# DRV8833.net
KiCad netlist of a schematic drawn in Altium Designer
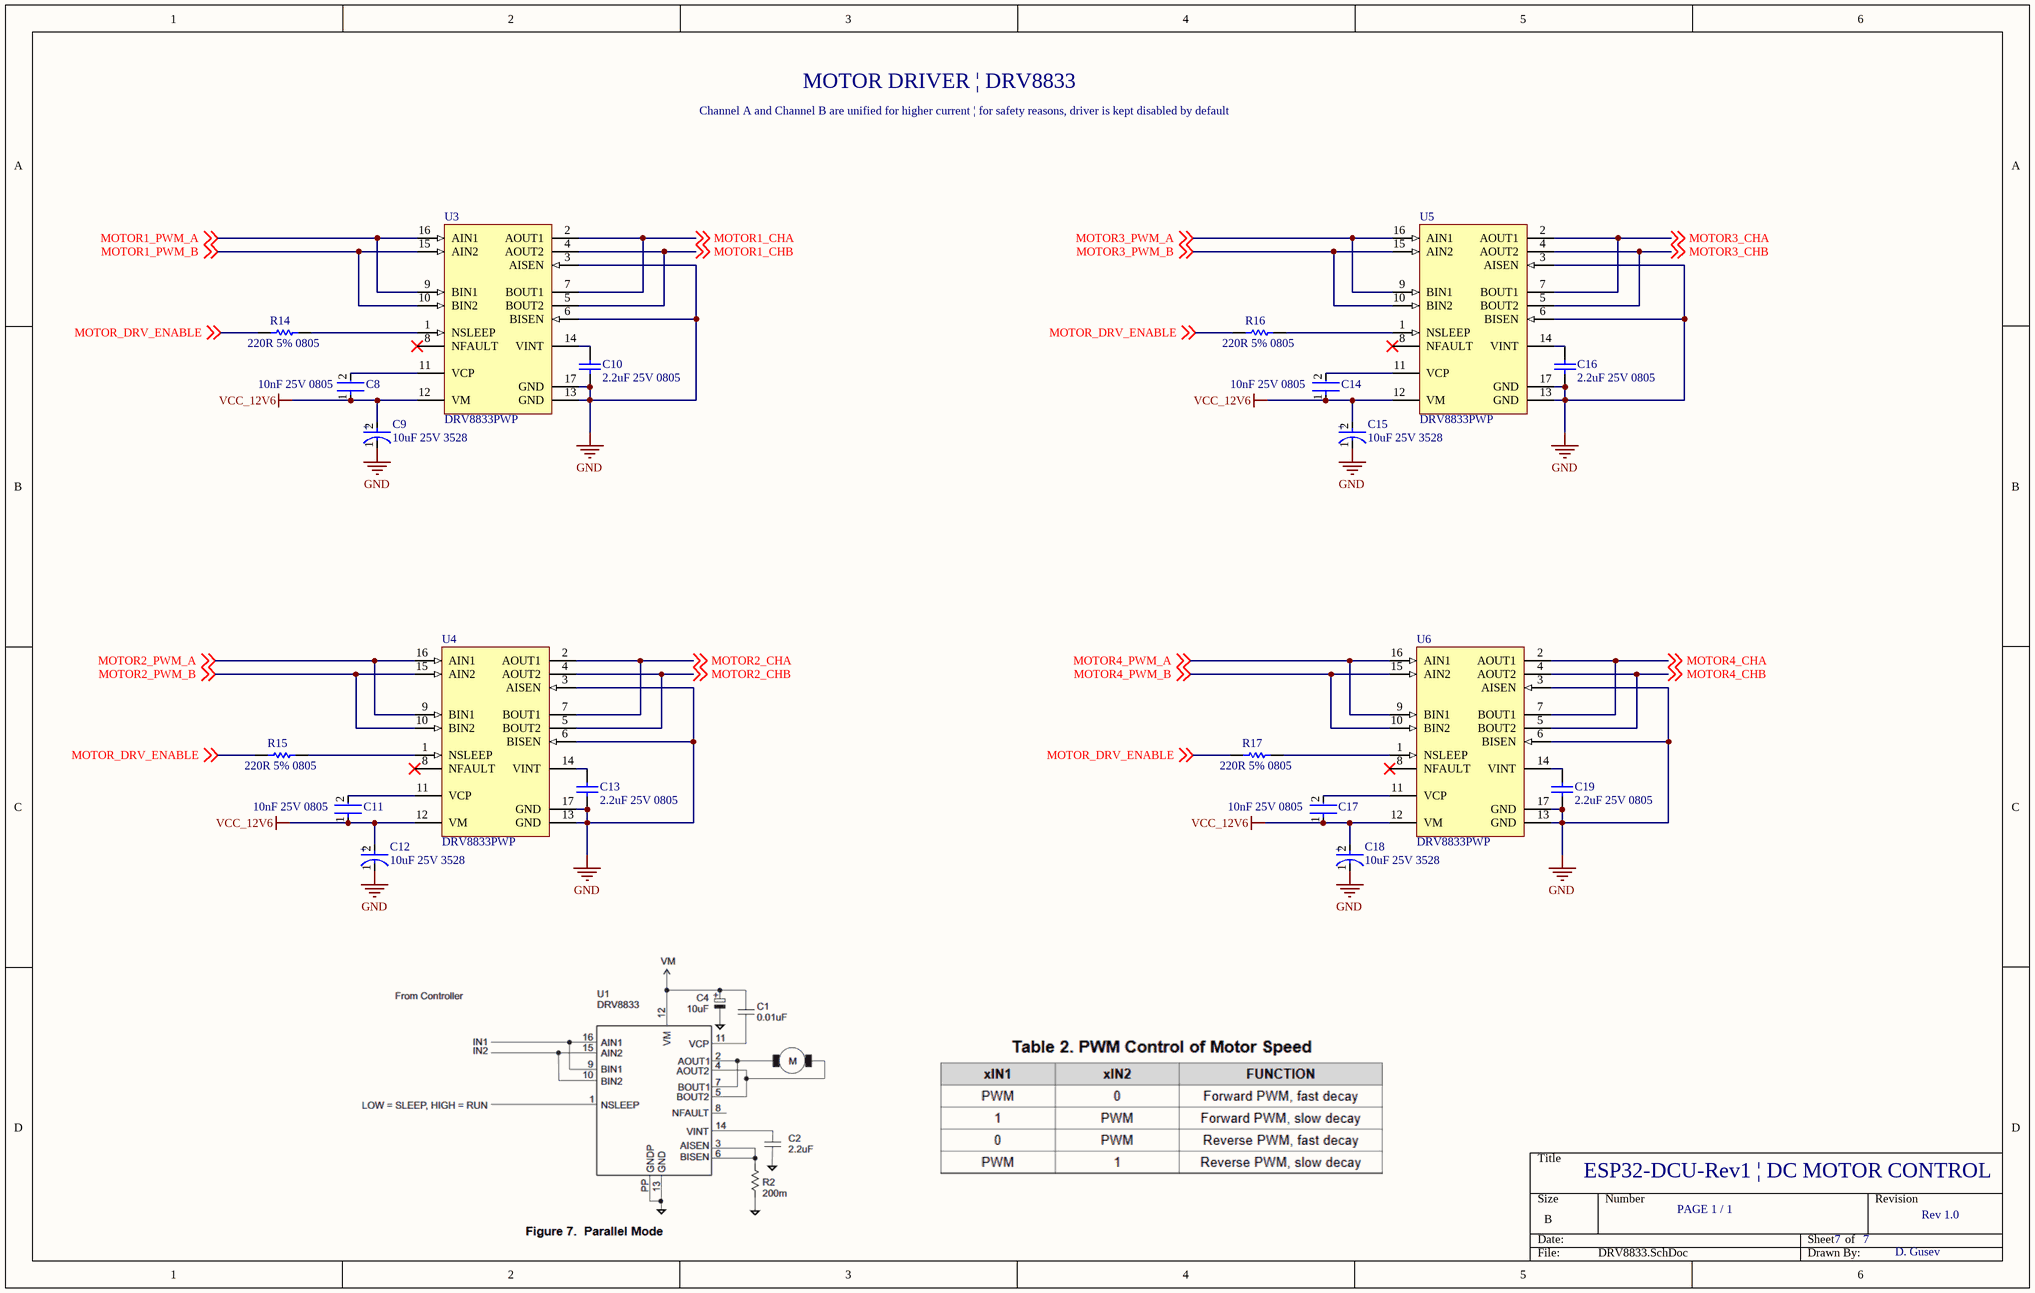
[diagram p0: DRV8833.SchDoc]

(export (version "E")
  (design (tool "Eeschema 10.0.6"))
  (components
    (comp (ref "C8")
      (value "10nF 25V 0805")
      (footprint "FP-C0805C-DN-MFG")
      (description "CAP CER 10000PF 25V 5% NP0 0805")
      (fields
        (field (name "OCTOPART") "https://octopart.com/c0805c103j3gactu-kemet-12563663")
        (field (name "TOLERANCE") "0.05")
      )
      (libsource (lib "Altium Content Vault") (part "b4654b650e69147ec39a6b967a45e02"))
    )
    (comp (ref "C9")
      (value "10uF 25V 3528")
      (footprint "FP-T491B106K025AT-MFG")
      (description "CAP TANT 10UF 10% 25V 1411")
      (fields (field (name "VOLTAGE") "25V") (field (name "TOLERANCE") "10%"))
      (libsource (lib "Altium Content Vault") (part "a00bbbee19879c290e62620ae7e47b1"))
    )
    (comp (ref "C10")
      (value "2.2uF 25V 0805")
      (footprint "CAPC2013X135X45ML10T25")
      (fields (field (name "PART NUMBER") "GRM21BF51E225ZA01L") (field (name "MANUFACTURER") "Murata"))
      (libsource (lib "Altium Content Vault") (part "CAP"))
    )
    (comp (ref "C11")
      (value "10nF 25V 0805")
      (footprint "FP-C0805C-DN-MFG")
      (description "CAP CER 10000PF 25V 5% NP0 0805")
      (fields
        (field (name "OCTOPART") "https://octopart.com/c0805c103j3gactu-kemet-12563663")
        (field (name "TOLERANCE") "0.05")
      )
      (libsource (lib "Altium Content Vault") (part "b4654b650e69147ec39a6b967a45e02"))
    )
    (comp (ref "C12")
      (value "10uF 25V 3528")
      (footprint "FP-T491B106K025AT-MFG")
      (description "CAP TANT 10UF 10% 25V 1411")
      (fields (field (name "VOLTAGE") "25V") (field (name "TOLERANCE") "10%"))
      (libsource (lib "Altium Content Vault") (part "a00bbbee19879c290e62620ae7e47b1"))
    )
    (comp (ref "C13")
      (value "2.2uF 25V 0805")
      (footprint "CAPC2013X135X45ML10T25")
      (fields (field (name "PART NUMBER") "GRM21BF51E225ZA01L") (field (name "MANUFACTURER") "Murata"))
      (libsource (lib "Altium Content Vault") (part "CAP"))
    )
    (comp (ref "C14")
      (value "10nF 25V 0805")
      (footprint "FP-C0805C-DN-MFG")
      (description "CAP CER 10000PF 25V 5% NP0 0805")
      (fields
        (field (name "OCTOPART") "https://octopart.com/c0805c103j3gactu-kemet-12563663")
        (field (name "TOLERANCE") "0.05")
      )
      (libsource (lib "Altium Content Vault") (part "b4654b650e69147ec39a6b967a45e02"))
    )
    (comp (ref "C15")
      (value "10uF 25V 3528")
      (footprint "FP-T491B106K025AT-MFG")
      (description "CAP TANT 10UF 10% 25V 1411")
      (fields (field (name "VOLTAGE") "25V") (field (name "TOLERANCE") "10%"))
      (libsource (lib "Altium Content Vault") (part "a00bbbee19879c290e62620ae7e47b1"))
    )
    (comp (ref "C16")
      (value "2.2uF 25V 0805")
      (footprint "CAPC2013X135X45ML10T25")
      (fields (field (name "PART NUMBER") "GRM21BF51E225ZA01L") (field (name "MANUFACTURER") "Murata"))
      (libsource (lib "Altium Content Vault") (part "CAP"))
    )
    (comp (ref "C17")
      (value "10nF 25V 0805")
      (footprint "FP-C0805C-DN-MFG")
      (description "CAP CER 10000PF 25V 5% NP0 0805")
      (fields
        (field (name "OCTOPART") "https://octopart.com/c0805c103j3gactu-kemet-12563663")
        (field (name "TOLERANCE") "0.05")
      )
      (libsource (lib "Altium Content Vault") (part "b4654b650e69147ec39a6b967a45e02"))
    )
    (comp (ref "C18")
      (value "10uF 25V 3528")
      (footprint "FP-T491B106K025AT-MFG")
      (description "CAP TANT 10UF 10% 25V 1411")
      (fields (field (name "VOLTAGE") "25V") (field (name "TOLERANCE") "10%"))
      (libsource (lib "Altium Content Vault") (part "a00bbbee19879c290e62620ae7e47b1"))
    )
    (comp (ref "C19")
      (value "2.2uF 25V 0805")
      (footprint "CAPC2013X135X45ML10T25")
      (fields (field (name "PART NUMBER") "GRM21BF51E225ZA01L") (field (name "MANUFACTURER") "Murata"))
      (libsource (lib "Altium Content Vault") (part "CAP"))
    )
    (comp (ref "R14")
      (value "220R 5% 0805")
      (footprint "RESC2013X60X40NL20T25")
      (fields (field (name "MANUFACTURER") "Panasonic") (field (name "PART NUMBER") "ERA6AEB221V"))
      (libsource (lib "Altium Content Vault") (part "RES"))
    )
    (comp (ref "R15")
      (value "220R 5% 0805")
      (footprint "RESC2013X60X40NL20T25")
      (fields (field (name "MANUFACTURER") "Panasonic") (field (name "PART NUMBER") "ERA6AEB221V"))
      (libsource (lib "Altium Content Vault") (part "RES"))
    )
    (comp (ref "R16")
      (value "220R 5% 0805")
      (footprint "RESC2013X60X40NL20T25")
      (fields (field (name "MANUFACTURER") "Panasonic") (field (name "PART NUMBER") "ERA6AEB221V"))
      (libsource (lib "Altium Content Vault") (part "RES"))
    )
    (comp (ref "R17")
      (value "220R 5% 0805")
      (footprint "RESC2013X60X40NL20T25")
      (fields (field (name "MANUFACTURER") "Panasonic") (field (name "PART NUMBER") "ERA6AEB221V"))
      (libsource (lib "Altium Content Vault") (part "RES"))
    )
    (comp (ref "U3")
      (value "DRV8833PWP")
      (footprint "PWP0016C_N")
      (fields (field (name "MANUFACTURER") "Texas Instruments"))
      (libsource (lib "Altium Content Vault") (part "TI-DRV8833PWP16-2370X2105TP"))
    )
    (comp (ref "U4")
      (value "DRV8833PWP")
      (footprint "PWP0016C_N")
      (fields (field (name "MANUFACTURER") "Texas Instruments"))
      (libsource (lib "Altium Content Vault") (part "TI-DRV8833PWP16-2370X2105TP"))
    )
    (comp (ref "U5")
      (value "DRV8833PWP")
      (footprint "PWP0016C_N")
      (fields (field (name "MANUFACTURER") "Texas Instruments"))
      (libsource (lib "Altium Content Vault") (part "TI-DRV8833PWP16-2370X2105TP"))
    )
    (comp (ref "U6")
      (value "DRV8833PWP")
      (footprint "PWP0016C_N")
      (fields (field (name "MANUFACTURER") "Texas Instruments"))
      (libsource (lib "Altium Content Vault") (part "TI-DRV8833PWP16-2370X2105TP"))
    )
  )
  (nets
    (net (code "1") (name "GND") (class "Default")
      (node (ref "C10") (pin "1") (pinfunction "1_1") (pintype "passive"))
      (node (ref "C12") (pin "1") (pinfunction "C_1") (pintype "passive"))
      (node (ref "C13") (pin "1") (pinfunction "1_1") (pintype "passive"))
      (node (ref "C15") (pin "1") (pinfunction "C_1") (pintype "passive"))
      (node (ref "C16") (pin "1") (pinfunction "1_1") (pintype "passive"))
      (node (ref "C18") (pin "1") (pinfunction "C_1") (pintype "passive"))
      (node (ref "C19") (pin "1") (pinfunction "1_1") (pintype "passive"))
      (node (ref "C9") (pin "1") (pinfunction "C_1") (pintype "passive"))
      (node (ref "U3") (pin "13") (pinfunction "GND_13") (pintype "power_in"))
      (node (ref "U3") (pin "17") (pinfunction "GND_17") (pintype "power_in"))
      (node (ref "U3") (pin "3") (pinfunction "AISEN_3") (pintype "input"))
      (node (ref "U3") (pin "6") (pinfunction "BISEN_6") (pintype "input"))
      (node (ref "U4") (pin "13") (pinfunction "GND_13") (pintype "power_in"))
      (node (ref "U4") (pin "17") (pinfunction "GND_17") (pintype "power_in"))
      (node (ref "U4") (pin "3") (pinfunction "AISEN_3") (pintype "input"))
      (node (ref "U4") (pin "6") (pinfunction "BISEN_6") (pintype "input"))
      (node (ref "U5") (pin "13") (pinfunction "GND_13") (pintype "power_in"))
      (node (ref "U5") (pin "17") (pinfunction "GND_17") (pintype "power_in"))
      (node (ref "U5") (pin "3") (pinfunction "AISEN_3") (pintype "input"))
      (node (ref "U5") (pin "6") (pinfunction "BISEN_6") (pintype "input"))
      (node (ref "U6") (pin "13") (pinfunction "GND_13") (pintype "power_in"))
      (node (ref "U6") (pin "17") (pinfunction "GND_17") (pintype "power_in"))
      (node (ref "U6") (pin "3") (pinfunction "AISEN_3") (pintype "input"))
      (node (ref "U6") (pin "6") (pinfunction "BISEN_6") (pintype "input"))
    )
    (net (code "2") (name "MOTOR1_CHA") (class "Default")
      (node (ref "U3") (pin "2") (pinfunction "AOUT1_2") (pintype "tri_state"))
      (node (ref "U3") (pin "7") (pinfunction "BOUT1_7") (pintype "tri_state"))
    )
    (net (code "3") (name "MOTOR1_CHB") (class "Default")
      (node (ref "U3") (pin "4") (pinfunction "AOUT2_4") (pintype "tri_state"))
      (node (ref "U3") (pin "5") (pinfunction "BOUT2_5") (pintype "tri_state"))
    )
    (net (code "4") (name "MOTOR1_PWM_A") (class "Default")
      (node (ref "U3") (pin "16") (pinfunction "AIN1_16") (pintype "input"))
      (node (ref "U3") (pin "9") (pinfunction "BIN1_9") (pintype "input"))
    )
    (net (code "5") (name "MOTOR1_PWM_B") (class "Default")
      (node (ref "U3") (pin "10") (pinfunction "BIN2_10") (pintype "input"))
      (node (ref "U3") (pin "15") (pinfunction "AIN2_15") (pintype "input"))
    )
    (net (code "6") (name "MOTOR2_CHA") (class "Default")
      (node (ref "U4") (pin "2") (pinfunction "AOUT1_2") (pintype "tri_state"))
      (node (ref "U4") (pin "7") (pinfunction "BOUT1_7") (pintype "tri_state"))
    )
    (net (code "7") (name "MOTOR2_CHB") (class "Default")
      (node (ref "U4") (pin "4") (pinfunction "AOUT2_4") (pintype "tri_state"))
      (node (ref "U4") (pin "5") (pinfunction "BOUT2_5") (pintype "tri_state"))
    )
    (net (code "8") (name "MOTOR2_PWM_A") (class "Default")
      (node (ref "U4") (pin "16") (pinfunction "AIN1_16") (pintype "input"))
      (node (ref "U4") (pin "9") (pinfunction "BIN1_9") (pintype "input"))
    )
    (net (code "9") (name "MOTOR2_PWM_B") (class "Default")
      (node (ref "U4") (pin "10") (pinfunction "BIN2_10") (pintype "input"))
      (node (ref "U4") (pin "15") (pinfunction "AIN2_15") (pintype "input"))
    )
    (net (code "10") (name "MOTOR3_CHA") (class "Default")
      (node (ref "U5") (pin "2") (pinfunction "AOUT1_2") (pintype "tri_state"))
      (node (ref "U5") (pin "7") (pinfunction "BOUT1_7") (pintype "tri_state"))
    )
    (net (code "11") (name "MOTOR3_CHB") (class "Default")
      (node (ref "U5") (pin "4") (pinfunction "AOUT2_4") (pintype "tri_state"))
      (node (ref "U5") (pin "5") (pinfunction "BOUT2_5") (pintype "tri_state"))
    )
    (net (code "12") (name "MOTOR3_PWM_A") (class "Default")
      (node (ref "U5") (pin "16") (pinfunction "AIN1_16") (pintype "input"))
      (node (ref "U5") (pin "9") (pinfunction "BIN1_9") (pintype "input"))
    )
    (net (code "13") (name "MOTOR3_PWM_B") (class "Default")
      (node (ref "U5") (pin "10") (pinfunction "BIN2_10") (pintype "input"))
      (node (ref "U5") (pin "15") (pinfunction "AIN2_15") (pintype "input"))
    )
    (net (code "14") (name "MOTOR4_CHA") (class "Default")
      (node (ref "U6") (pin "2") (pinfunction "AOUT1_2") (pintype "tri_state"))
      (node (ref "U6") (pin "7") (pinfunction "BOUT1_7") (pintype "tri_state"))
    )
    (net (code "15") (name "MOTOR4_CHB") (class "Default")
      (node (ref "U6") (pin "4") (pinfunction "AOUT2_4") (pintype "tri_state"))
      (node (ref "U6") (pin "5") (pinfunction "BOUT2_5") (pintype "tri_state"))
    )
    (net (code "16") (name "MOTOR4_PWM_A") (class "Default")
      (node (ref "U6") (pin "16") (pinfunction "AIN1_16") (pintype "input"))
      (node (ref "U6") (pin "9") (pinfunction "BIN1_9") (pintype "input"))
    )
    (net (code "17") (name "MOTOR4_PWM_B") (class "Default")
      (node (ref "U6") (pin "10") (pinfunction "BIN2_10") (pintype "input"))
      (node (ref "U6") (pin "15") (pinfunction "AIN2_15") (pintype "input"))
    )
    (net (code "18") (name "MOTOR_DRV_ENABLE") (class "Default")
      (node (ref "R14") (pin "1") (pinfunction "1_1") (pintype "passive"))
      (node (ref "R15") (pin "1") (pinfunction "1_1") (pintype "passive"))
      (node (ref "R16") (pin "1") (pinfunction "1_1") (pintype "passive"))
      (node (ref "R17") (pin "1") (pinfunction "1_1") (pintype "passive"))
    )
    (net (code "19") (name "Net-(U3-NSLEEP)") (class "Default")
      (node (ref "R14") (pin "2") (pinfunction "2_2") (pintype "passive"))
      (node (ref "U3") (pin "1") (pinfunction "NSLEEP_1") (pintype "input"))
    )
    (net (code "20") (name "Net-(U3-VCP)") (class "Default")
      (node (ref "C8") (pin "2") (pinfunction "2_2") (pintype "passive"))
      (node (ref "U3") (pin "11") (pinfunction "VCP_11") (pintype "passive"))
    )
    (net (code "21") (name "Net-(U3-VINT)") (class "Default")
      (node (ref "C10") (pin "2") (pinfunction "2_2") (pintype "passive"))
      (node (ref "U3") (pin "14") (pinfunction "VINT_14") (pintype "passive"))
    )
    (net (code "22") (name "Net-(U4-NSLEEP)") (class "Default")
      (node (ref "R15") (pin "2") (pinfunction "2_2") (pintype "passive"))
      (node (ref "U4") (pin "1") (pinfunction "NSLEEP_1") (pintype "input"))
    )
    (net (code "23") (name "Net-(U4-VCP)") (class "Default")
      (node (ref "C11") (pin "2") (pinfunction "2_2") (pintype "passive"))
      (node (ref "U4") (pin "11") (pinfunction "VCP_11") (pintype "passive"))
    )
    (net (code "24") (name "Net-(U4-VINT)") (class "Default")
      (node (ref "C13") (pin "2") (pinfunction "2_2") (pintype "passive"))
      (node (ref "U4") (pin "14") (pinfunction "VINT_14") (pintype "passive"))
    )
    (net (code "25") (name "Net-(U5-NSLEEP)") (class "Default")
      (node (ref "R16") (pin "2") (pinfunction "2_2") (pintype "passive"))
      (node (ref "U5") (pin "1") (pinfunction "NSLEEP_1") (pintype "input"))
    )
    (net (code "26") (name "Net-(U5-VCP)") (class "Default")
      (node (ref "C14") (pin "2") (pinfunction "2_2") (pintype "passive"))
      (node (ref "U5") (pin "11") (pinfunction "VCP_11") (pintype "passive"))
    )
    (net (code "27") (name "Net-(U5-VINT)") (class "Default")
      (node (ref "C16") (pin "2") (pinfunction "2_2") (pintype "passive"))
      (node (ref "U5") (pin "14") (pinfunction "VINT_14") (pintype "passive"))
    )
    (net (code "28") (name "Net-(U6-NSLEEP)") (class "Default")
      (node (ref "R17") (pin "2") (pinfunction "2_2") (pintype "passive"))
      (node (ref "U6") (pin "1") (pinfunction "NSLEEP_1") (pintype "input"))
    )
    (net (code "29") (name "Net-(U6-VCP)") (class "Default")
      (node (ref "C17") (pin "2") (pinfunction "2_2") (pintype "passive"))
      (node (ref "U6") (pin "11") (pinfunction "VCP_11") (pintype "passive"))
    )
    (net (code "30") (name "Net-(U6-VINT)") (class "Default")
      (node (ref "C19") (pin "2") (pinfunction "2_2") (pintype "passive"))
      (node (ref "U6") (pin "14") (pinfunction "VINT_14") (pintype "passive"))
    )
    (net (code "31") (name "VCC_12V6") (class "Default")
      (node (ref "C11") (pin "1") (pinfunction "1_1") (pintype "passive"))
      (node (ref "C12") (pin "2") (pinfunction "A_2") (pintype "passive"))
      (node (ref "C14") (pin "1") (pinfunction "1_1") (pintype "passive"))
      (node (ref "C15") (pin "2") (pinfunction "A_2") (pintype "passive"))
      (node (ref "C17") (pin "1") (pinfunction "1_1") (pintype "passive"))
      (node (ref "C18") (pin "2") (pinfunction "A_2") (pintype "passive"))
      (node (ref "C8") (pin "1") (pinfunction "1_1") (pintype "passive"))
      (node (ref "C9") (pin "2") (pinfunction "A_2") (pintype "passive"))
      (node (ref "U3") (pin "12") (pinfunction "VM_12") (pintype "power_in"))
      (node (ref "U4") (pin "12") (pinfunction "VM_12") (pintype "power_in"))
      (node (ref "U5") (pin "12") (pinfunction "VM_12") (pintype "power_in"))
      (node (ref "U6") (pin "12") (pinfunction "VM_12") (pintype "power_in"))
    )
    (net (code "32") (name "unconnected-(U3-NFAULT-Pad8)") (class "Default")
      (node (ref "U3") (pin "8") (pinfunction "NFAULT_8") (pintype "open_collector+no_connect"))
    )
    (net (code "33") (name "unconnected-(U4-NFAULT-Pad8)") (class "Default")
      (node (ref "U4") (pin "8") (pinfunction "NFAULT_8") (pintype "open_collector+no_connect"))
    )
    (net (code "34") (name "unconnected-(U5-NFAULT-Pad8)") (class "Default")
      (node (ref "U5") (pin "8") (pinfunction "NFAULT_8") (pintype "open_collector+no_connect"))
    )
    (net (code "35") (name "unconnected-(U6-NFAULT-Pad8)") (class "Default")
      (node (ref "U6") (pin "8") (pinfunction "NFAULT_8") (pintype "open_collector+no_connect"))
    )
  )
)
